# LTM455_sch.net
KiCad netlist of a schematic drawn in Altium Designer
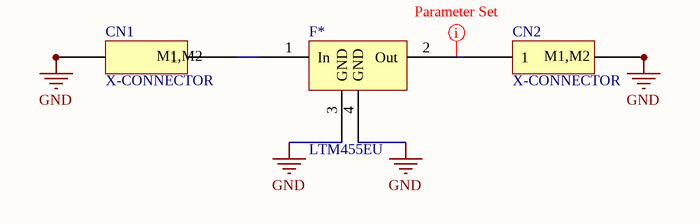
[diagram p0: LTM455_sch.SchDoc]

(export (version "E")
  (design (tool "Eeschema 10.0.6"))
  (components
    (comp (ref "CN1")
      (value "X-CONNECTOR")
      (footprint "X-CONNECTOR-PCB")
      (description "CONECTOR PARA MÓDULOS X MICROWAVE")
      (libsource (lib "(LR)²") (part "X-CONNECTOR"))
    )
    (comp (ref "CN2")
      (value "X-CONNECTOR")
      (footprint "X-CONNECTOR-PCB")
      (description "CONECTOR PARA MÓDULOS X MICROWAVE")
      (libsource (lib "") (part "X-CONNECTOR_1"))
    )
    (comp (ref "F*")
      (value "LTM455EU")
      (footprint "New footprint 1")
      (description "Ceramic band pass filter fc = 455khz")
      (libsource (lib "IMBEL") (part "LTM455"))
    )
  )
  (nets
    (net (code "1") (name "GND") (class "Default")
      (node (ref "CN1") (pin "M1") (pinfunction "M1_M1") (pintype "passive"))
      (node (ref "CN1") (pin "M2") (pinfunction "M2_M2") (pintype "passive"))
      (node (ref "CN2") (pin "M1") (pinfunction "M1_M1") (pintype "passive"))
      (node (ref "CN2") (pin "M2") (pinfunction "M2_M2") (pintype "passive"))
      (node (ref "F*") (pin "3") (pinfunction "GND_3") (pintype "passive"))
      (node (ref "F*") (pin "4") (pinfunction "GND_4") (pintype "passive"))
    )
    (net (code "2") (name "Net-(F*-In)") (class "Default")
      (node (ref "CN1") (pin "1") (pinfunction "1_1") (pintype "passive"))
      (node (ref "F*") (pin "1") (pinfunction "In_1") (pintype "passive"))
    )
    (net (code "3") (name "Net-(F*-Out)") (class "Default")
      (node (ref "CN2") (pin "1") (pinfunction "1_1") (pintype "passive"))
      (node (ref "F*") (pin "2") (pinfunction "Out_2") (pintype "passive"))
    )
  )
)
